# LM74910H_PINOUT.net
KiCad netlist of a schematic drawn in Altium Designer
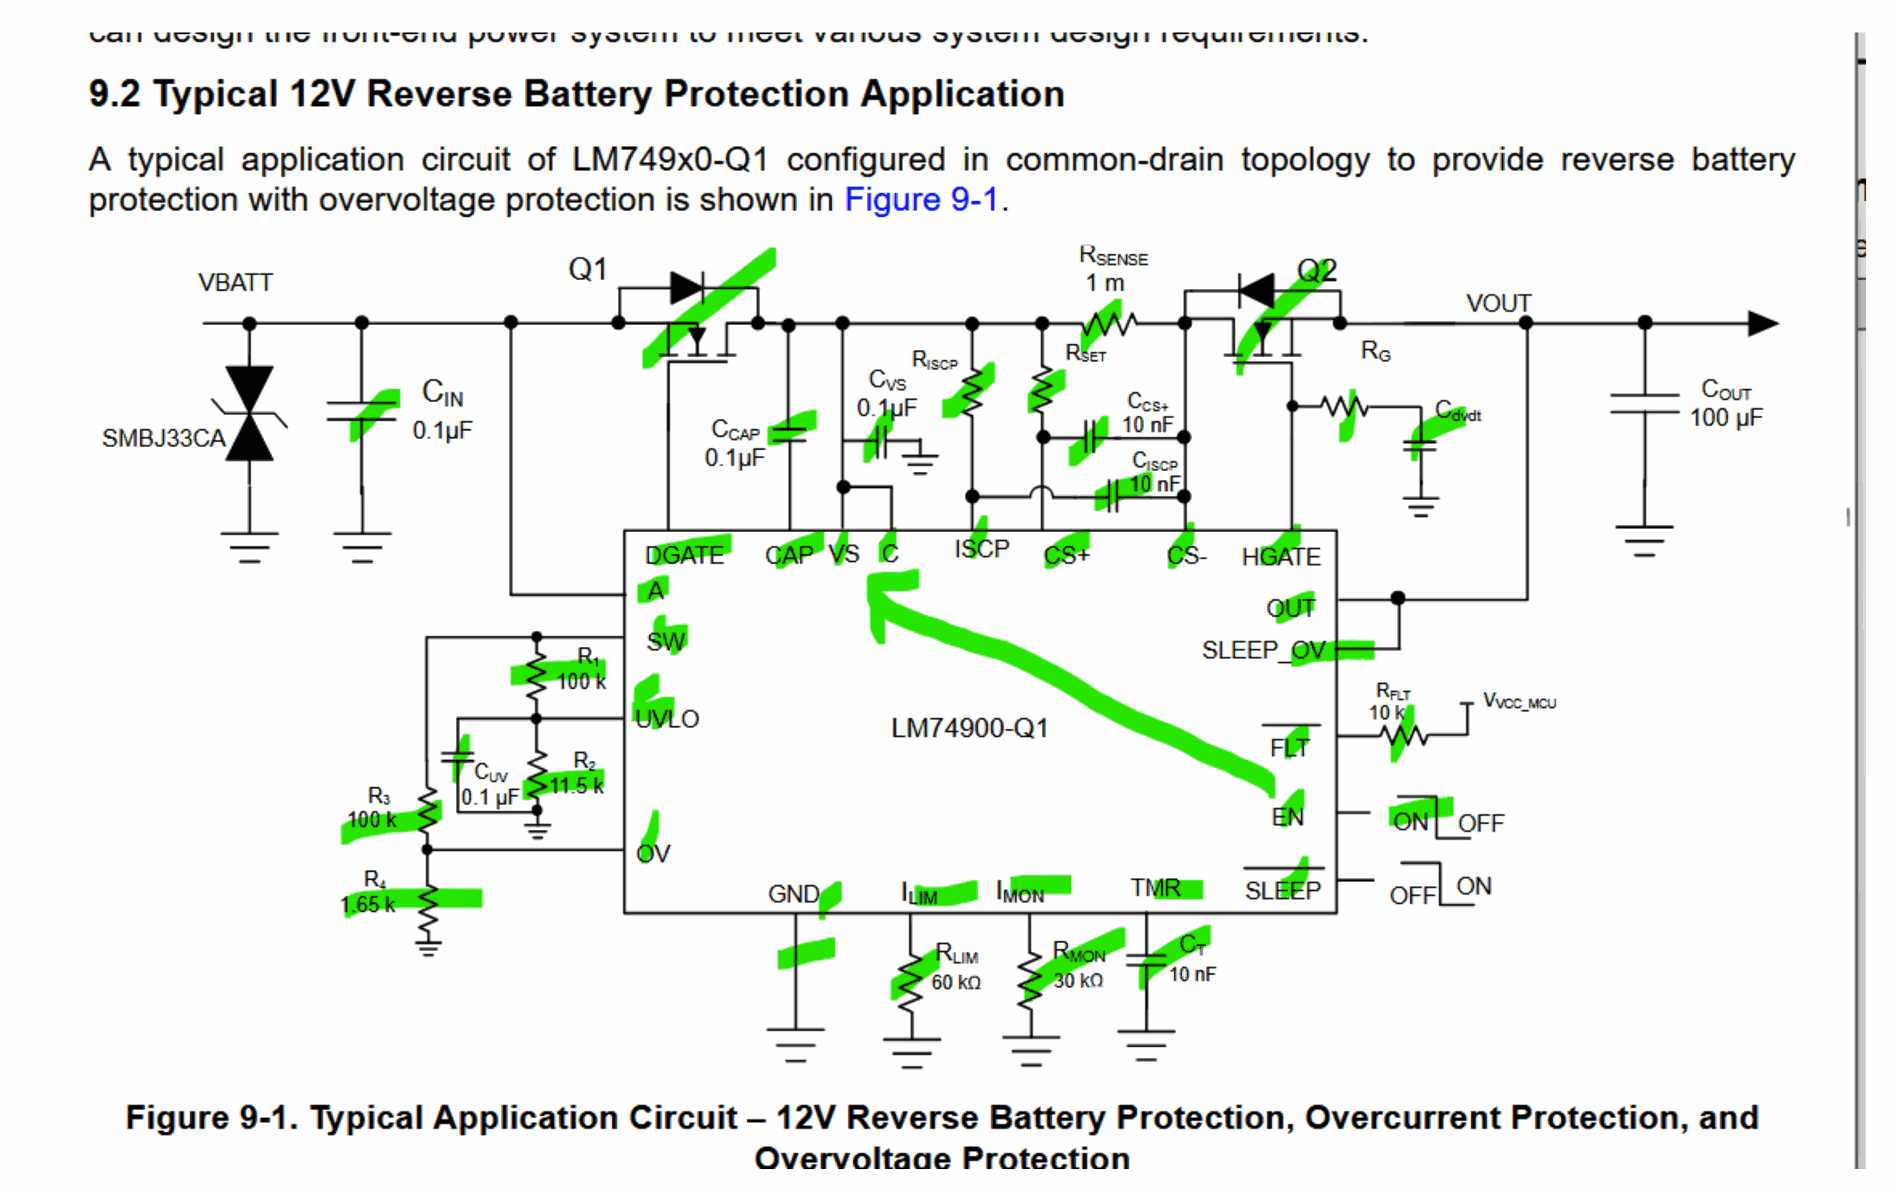
[diagram p0: LM74910H_PINOUT.SchDoc, top]
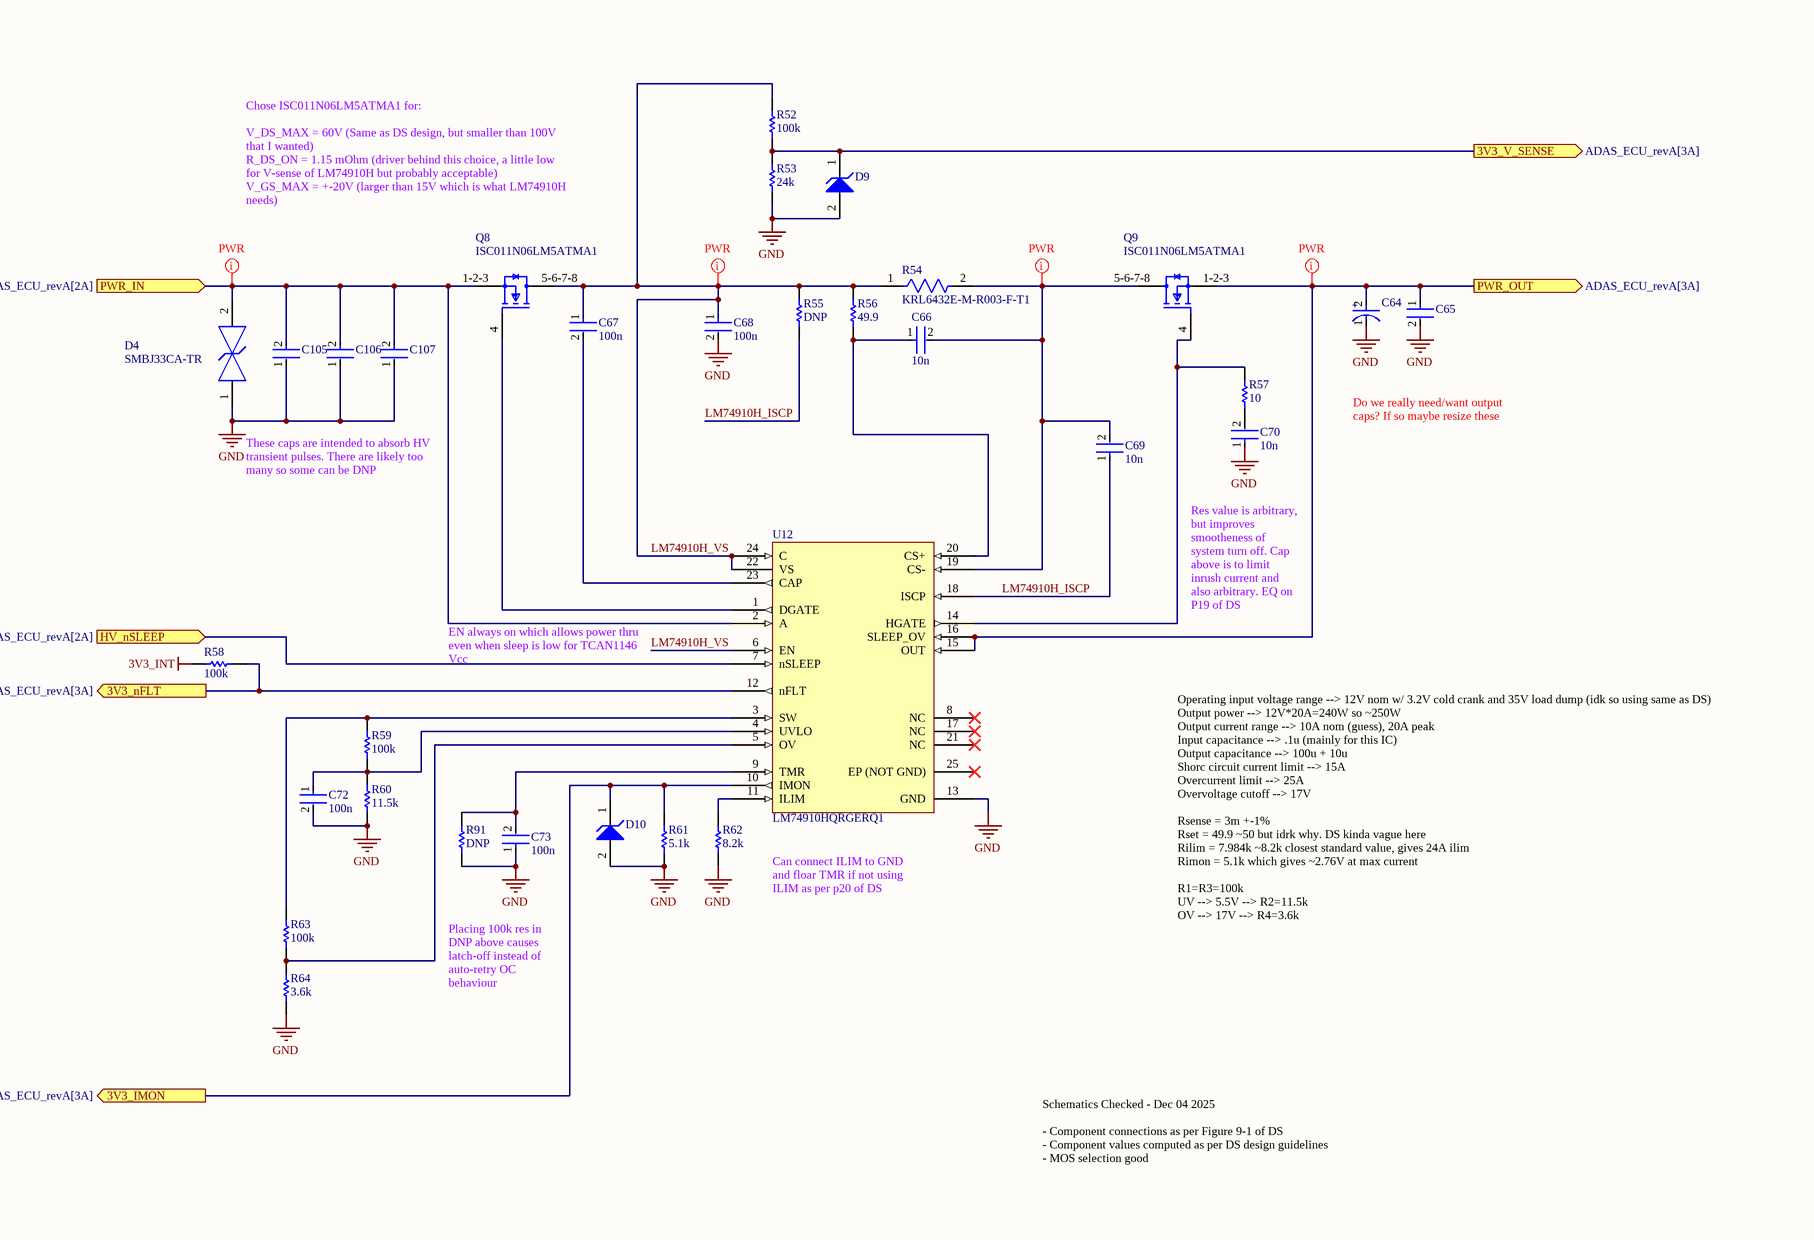
[diagram p1: LM74910H_PINOUT.SchDoc, bottom]

(export (version "E")
  (design (tool "Eeschema 10.0.6"))
  (components
    (comp (ref "C64")
      (value "EEE-FK1H100UR")
      (footprint "FP-FKC-MFG")
      (description "CAP ALUM 10UF 20% 50V SMD")
      (fields (field (name "TOLERANCE") "20%") (field (name "VOLTAGE") "50V"))
      (libsource (lib "Altium Content Vault") (part "a00bbbee19879c290e62620ae7e47b1"))
    )
    (comp (ref "C65")
      (value "12103D106KAT2A")
      (footprint "FP-1210-L_3_3_0_4-W_2_5_0-MFG")
      (description "General Purpose Ceramic Capacitor, 1210, 10uF, 10%, X5R, 15%, 25V")
      (fields (field (name "VOLTAGE") "25V") (field (name "TOLERANCE") "10%"))
      (libsource (lib "Altium Content Vault") (part "b4654b650e69147ec39a6b967a45e02"))
    )
    (comp (ref "C66")
      (value "10n")
      (footprint "FP-0402-L_1_0_0_05-W_0_5-IPC_A")
      (description "LARGE PADS, 0402 CAP, CHANGE COMMENT TO MATCH REAL P/N")
      (libsource (lib "Space Concordia") (part "b4654b650e69147ec39a6b967a45e02"))
    )
    (comp (ref "C67")
      (value "100n")
      (footprint "FP-0402-L_1_0_0_05-W_0_5-IPC_A")
      (description "LARGE PADS, 0402 CAP, CHANGE COMMENT TO MATCH REAL P/N")
      (libsource (lib "Space Concordia") (part "b4654b650e69147ec39a6b967a45e02"))
    )
    (comp (ref "C68")
      (value "100n")
      (footprint "FP-0402-L_1_0_0_05-W_0_5-IPC_A")
      (description "LARGE PADS, 0402 CAP, CHANGE COMMENT TO MATCH REAL P/N")
      (libsource (lib "Space Concordia") (part "b4654b650e69147ec39a6b967a45e02"))
    )
    (comp (ref "C69")
      (value "10n")
      (footprint "FP-0402-L_1_0_0_05-W_0_5-IPC_A")
      (description "LARGE PADS, 0402 CAP, CHANGE COMMENT TO MATCH REAL P/N")
      (libsource (lib "Space Concordia") (part "b4654b650e69147ec39a6b967a45e02"))
    )
    (comp (ref "C70")
      (value "10n")
      (footprint "FP-0402-L_1_0_0_05-W_0_5-IPC_A")
      (description "LARGE PADS, 0402 CAP, CHANGE COMMENT TO MATCH REAL P/N")
      (libsource (lib "Space Concordia") (part "b4654b650e69147ec39a6b967a45e02"))
    )
    (comp (ref "C72")
      (value "100n")
      (footprint "FP-0402-L_1_0_0_05-W_0_5-IPC_A")
      (description "LARGE PADS, 0402 CAP, CHANGE COMMENT TO MATCH REAL P/N")
      (libsource (lib "Space Concordia") (part "b4654b650e69147ec39a6b967a45e02"))
    )
    (comp (ref "C73")
      (value "100n")
      (footprint "FP-0402-L_1_0_0_05-W_0_5-IPC_A")
      (description "LARGE PADS, 0402 CAP, CHANGE COMMENT TO MATCH REAL P/N")
      (libsource (lib "Space Concordia") (part "b4654b650e69147ec39a6b967a45e02"))
    )
    (comp (ref "C105")
      (value "AC1210KKX7R0BB104")
      (footprint "FP-AC1210-0_85-MFG")
      (description "CAP CER 0.1UF 100V X7R 1210")
      (fields (field (name "MANUFACTURER") "Yageo") (field (name "TOLERANCE") "0.1"))
      (libsource (lib "Altium Content Vault") (part "236180d848d6139a670b325ea6854c9"))
    )
    (comp (ref "C106")
      (value "AC1210KKX7R0BB104")
      (footprint "FP-AC1210-0_85-MFG")
      (description "CAP CER 0.1UF 100V X7R 1210")
      (fields (field (name "MANUFACTURER") "Yageo") (field (name "TOLERANCE") "0.1"))
      (libsource (lib "Altium Content Vault") (part "236180d848d6139a670b325ea6854c9"))
    )
    (comp (ref "C107")
      (value "AC1210KKX7R0BB104")
      (footprint "FP-AC1210-0_85-MFG")
      (description "CAP CER 0.1UF 100V X7R 1210")
      (fields (field (name "MANUFACTURER") "Yageo") (field (name "TOLERANCE") "0.1"))
      (libsource (lib "Altium Content Vault") (part "236180d848d6139a670b325ea6854c9"))
    )
    (comp (ref "D4")
      (value "SMBJ33CA-TR")
      (footprint "FP-SMB-CA-MFG")
      (description "TVS DIODE 33V 69.7V SMB")
      (fields
        (field (name "OCTOPART") "https://octopart.com/smbj33ca-tr-stmicroelectronics-347069")
        (field (name "MANUFACTURER") "STMicroelectronics")
      )
      (libsource (lib "Altium Content Vault") (part "11bd9d59d340f0612179daf16ad9b72"))
    )
    (comp (ref "D9")
      (value "DNP/MM5Z3V3T1G")
      (footprint "ONSC-SOD-523-2-502-01_V")
      (description "Zener Voltage Regulator, 500 mW, 2-Pin SOD-523, Pb-Free, Tape and Reel")
      (fields (field (name "MANUFACTURER") "On Semiconductor") (field (name "PARTNUMBER") "MM5Z3V3T1G"))
      (libsource (lib "Altium Content Vault") (part "ONSC-K1A2-2"))
    )
    (comp (ref "D10")
      (value "DNP/MM5Z3V3T1G")
      (footprint "ONSC-SOD-523-2-502-01_V")
      (description "Zener Voltage Regulator, 500 mW, 2-Pin SOD-523, Pb-Free, Tape and Reel")
      (fields (field (name "MANUFACTURER") "On Semiconductor") (field (name "PARTNUMBER") "MM5Z3V3T1G"))
      (libsource (lib "Altium Content Vault") (part "ONSC-K1A2-2"))
    )
    (comp (ref "Q8")
      (value "ISC011N06LM5ATMA1")
      (footprint "FP-PG-TDSON-8-MFG")
      (description "TRENCH 40<-<100V PG-TDSON-8")
      (libsource (lib "Altium Content Vault") (part "3085234d4498bcd04bc7e5400bb7c96"))
    )
    (comp (ref "Q9")
      (value "ISC011N06LM5ATMA1")
      (footprint "FP-PG-TDSON-8-MFG")
      (description "TRENCH 40<-<100V PG-TDSON-8")
      (libsource (lib "Altium Content Vault") (part "3085234d4498bcd04bc7e5400bb7c96"))
    )
    (comp (ref "R52")
      (value "100k")
      (footprint "R0603B")
      (description "Resistor")
      (libsource (lib "Space Concordia") (part "Resistor"))
    )
    (comp (ref "R53")
      (value "24k")
      (footprint "R0603B")
      (description "Resistor")
      (libsource (lib "Space Concordia") (part "Resistor"))
    )
    (comp (ref "R54")
      (value "KRL6432E-M-R003-F-T1")
      (footprint "FP-KRL6432E-MFG")
      (description "KRL6432E-M-R003-F-T1 Metal Foil Low Resistance Chip Resistor (long-side terminal), 2512, RoHS")
      (fields (field (name "TOLERANCE") "1%"))
      (libsource (lib "Altium Content Vault") (part "1029c3af85768c4190bb7ad29bc67b5"))
    )
    (comp (ref "R55")
      (value "DNP")
      (footprint "R0603B")
      (description "Resistor")
      (libsource (lib "Space Concordia") (part "Resistor"))
    )
    (comp (ref "R56")
      (value "49.9")
      (footprint "R0603B")
      (description "Resistor")
      (libsource (lib "Space Concordia") (part "Resistor"))
    )
    (comp (ref "R57")
      (value "10")
      (footprint "R0603B")
      (description "Resistor")
      (libsource (lib "Space Concordia") (part "Resistor"))
    )
    (comp (ref "R58")
      (value "100k")
      (footprint "R0603B")
      (description "Resistor")
      (libsource (lib "Space Concordia") (part "Resistor"))
    )
    (comp (ref "R59")
      (value "100k")
      (footprint "R0603B")
      (description "Resistor")
      (libsource (lib "Space Concordia") (part "Resistor"))
    )
    (comp (ref "R60")
      (value "11.5k")
      (footprint "R0603B")
      (description "Resistor")
      (libsource (lib "Space Concordia") (part "Resistor"))
    )
    (comp (ref "R61")
      (value "5.1k")
      (footprint "R0603B")
      (description "Resistor")
      (libsource (lib "Space Concordia") (part "Resistor"))
    )
    (comp (ref "R62")
      (value "8.2k")
      (footprint "R0603B")
      (description "Resistor")
      (libsource (lib "Space Concordia") (part "Resistor"))
    )
    (comp (ref "R63")
      (value "100k")
      (footprint "R0603B")
      (description "Resistor")
      (libsource (lib "Space Concordia") (part "Resistor"))
    )
    (comp (ref "R64")
      (value "3.6k")
      (footprint "R0603B")
      (description "Resistor")
      (libsource (lib "Space Concordia") (part "Resistor"))
    )
    (comp (ref "R91")
      (value "DNP")
      (footprint "R0603B")
      (description "Resistor")
      (libsource (lib "Space Concordia") (part "Resistor"))
    )
    (comp (ref "U12")
      (value "LM74910HQRGERQ1")
      (footprint "QFN50P400X400X100_HS-25N")
      (libsource (lib "Space Concordia") (part "LM74910HQRGERQ1"))
    )
  )
  (nets
    (net (code "1") (name "/3V3_IMON") (class "Default")
      (node (ref "D10") (pin "1") (pinfunction "K_1") (pintype "passive"))
      (node (ref "R61") (pin "2") (pinfunction "2_2") (pintype "passive"))
      (node (ref "U12") (pin "10") (pinfunction "IMON_10") (pintype "output"))
    )
    (net (code "2") (name "/3V3_V_SENSE") (class "Default")
      (node (ref "D9") (pin "1") (pinfunction "K_1") (pintype "passive"))
      (node (ref "R52") (pin "1") (pinfunction "1_1") (pintype "passive"))
      (node (ref "R53") (pin "2") (pinfunction "2_2") (pintype "passive"))
    )
    (net (code "3") (name "/3V3_nFLT") (class "Default")
      (node (ref "R58") (pin "1") (pinfunction "1_1") (pintype "passive"))
      (node (ref "U12") (pin "12") (pinfunction "nFLT_12") (pintype "output"))
    )
    (net (code "4") (name "/HV_nSLEEP") (class "Default")
      (node (ref "U12") (pin "7") (pinfunction "nSLEEP_7") (pintype "input"))
    )
    (net (code "5") (name "/LM74910H_ISCP") (class "Default")
      (node (ref "C69") (pin "1") (pinfunction "1_1") (pintype "passive"))
      (node (ref "R55") (pin "1") (pinfunction "1_1") (pintype "passive"))
      (node (ref "U12") (pin "18") (pinfunction "ISCP_18") (pintype "input"))
    )
    (net (code "6") (name "/LM74910H_VS") (class "Default")
      (node (ref "C67") (pin "1") (pinfunction "1_1") (pintype "passive"))
      (node (ref "C68") (pin "1") (pinfunction "1_1") (pintype "passive"))
      (node (ref "Q8") (pin "5-6-7-8") (pinfunction "D_5-6-7-8") (pintype "passive"))
      (node (ref "R52") (pin "2") (pinfunction "2_2") (pintype "passive"))
      (node (ref "R54") (pin "1") (pinfunction "1_1") (pintype "passive"))
      (node (ref "R55") (pin "2") (pinfunction "2_2") (pintype "passive"))
      (node (ref "R56") (pin "2") (pinfunction "2_2") (pintype "passive"))
      (node (ref "U12") (pin "22") (pinfunction "VS_22") (pintype "power_in"))
      (node (ref "U12") (pin "24") (pinfunction "C_24") (pintype "input"))
      (node (ref "U12") (pin "6") (pinfunction "EN_6") (pintype "input"))
    )
    (net (code "7") (name "/PWR_IN") (class "Default")
      (node (ref "C105") (pin "2") (pinfunction "2_2") (pintype "passive"))
      (node (ref "C106") (pin "2") (pinfunction "2_2") (pintype "passive"))
      (node (ref "C107") (pin "2") (pinfunction "2_2") (pintype "passive"))
      (node (ref "D4") (pin "2") (pinfunction "2_2") (pintype "passive"))
      (node (ref "Q8") (pin "1-2-3") (pinfunction "S_1-2-3") (pintype "passive"))
      (node (ref "U12") (pin "2") (pinfunction "A_2") (pintype "input"))
    )
    (net (code "8") (name "/PWR_OUT") (class "Default")
      (node (ref "C64") (pin "2") (pinfunction "A_2") (pintype "passive"))
      (node (ref "C65") (pin "1") (pinfunction "1_1") (pintype "passive"))
      (node (ref "Q9") (pin "1-2-3") (pinfunction "S_1-2-3") (pintype "passive"))
      (node (ref "U12") (pin "15") (pinfunction "OUT_15") (pintype "input"))
      (node (ref "U12") (pin "16") (pinfunction "SLEEP_OV_16") (pintype "input"))
    )
    (net (code "9") (name "3V3_INT") (class "Default")
      (node (ref "R58") (pin "2") (pinfunction "2_2") (pintype "passive"))
    )
    (net (code "10") (name "GND") (class "Default")
      (node (ref "C105") (pin "1") (pinfunction "1_1") (pintype "passive"))
      (node (ref "C106") (pin "1") (pinfunction "1_1") (pintype "passive"))
      (node (ref "C107") (pin "1") (pinfunction "1_1") (pintype "passive"))
      (node (ref "C64") (pin "1") (pinfunction "C_1") (pintype "passive"))
      (node (ref "C65") (pin "2") (pinfunction "2_2") (pintype "passive"))
      (node (ref "C68") (pin "2") (pinfunction "2_2") (pintype "passive"))
      (node (ref "C70") (pin "1") (pinfunction "1_1") (pintype "passive"))
      (node (ref "C72") (pin "2") (pinfunction "2_2") (pintype "passive"))
      (node (ref "C73") (pin "1") (pinfunction "1_1") (pintype "passive"))
      (node (ref "D10") (pin "2") (pinfunction "A_2") (pintype "passive"))
      (node (ref "D4") (pin "1") (pinfunction "1_1") (pintype "passive"))
      (node (ref "D9") (pin "2") (pinfunction "A_2") (pintype "passive"))
      (node (ref "R53") (pin "1") (pinfunction "1_1") (pintype "passive"))
      (node (ref "R60") (pin "1") (pinfunction "1_1") (pintype "passive"))
      (node (ref "R61") (pin "1") (pinfunction "1_1") (pintype "passive"))
      (node (ref "R62") (pin "1") (pinfunction "1_1") (pintype "passive"))
      (node (ref "R64") (pin "1") (pinfunction "1_1") (pintype "passive"))
      (node (ref "R91") (pin "1") (pinfunction "1_1") (pintype "passive"))
      (node (ref "U12") (pin "13") (pinfunction "GND_13") (pintype "power_in"))
    )
    (net (code "11") (name "Net-(C70-Pad2)") (class "Default")
      (node (ref "C70") (pin "2") (pinfunction "2_2") (pintype "passive"))
      (node (ref "R57") (pin "1") (pinfunction "1_1") (pintype "passive"))
    )
    (net (code "12") (name "Net-(Q8-G)") (class "Default")
      (node (ref "Q8") (pin "4") (pinfunction "G_4") (pintype "passive"))
      (node (ref "U12") (pin "1") (pinfunction "DGATE_1") (pintype "output"))
    )
    (net (code "13") (name "Net-(Q9-D)") (class "Default")
      (node (ref "C66") (pin "2") (pinfunction "2_2") (pintype "passive"))
      (node (ref "C69") (pin "2") (pinfunction "2_2") (pintype "passive"))
      (node (ref "Q9") (pin "5-6-7-8") (pinfunction "D_5-6-7-8") (pintype "passive"))
      (node (ref "R54") (pin "2") (pinfunction "2_2") (pintype "passive"))
      (node (ref "U12") (pin "19") (pinfunction "CS-_19") (pintype "input"))
    )
    (net (code "14") (name "Net-(Q9-G)") (class "Default")
      (node (ref "Q9") (pin "4") (pinfunction "G_4") (pintype "passive"))
      (node (ref "R57") (pin "2") (pinfunction "2_2") (pintype "passive"))
      (node (ref "U12") (pin "14") (pinfunction "HGATE_14") (pintype "output"))
    )
    (net (code "15") (name "Net-(U12-CAP)") (class "Default")
      (node (ref "C67") (pin "2") (pinfunction "2_2") (pintype "passive"))
      (node (ref "U12") (pin "23") (pinfunction "CAP_23") (pintype "output"))
    )
    (net (code "16") (name "Net-(U12-CS+)") (class "Default")
      (node (ref "C66") (pin "1") (pinfunction "1_1") (pintype "passive"))
      (node (ref "R56") (pin "1") (pinfunction "1_1") (pintype "passive"))
      (node (ref "U12") (pin "20") (pinfunction "CS+_20") (pintype "input"))
    )
    (net (code "17") (name "Net-(U12-ILIM)") (class "Default")
      (node (ref "R62") (pin "2") (pinfunction "2_2") (pintype "passive"))
      (node (ref "U12") (pin "11") (pinfunction "ILIM_11") (pintype "input"))
    )
    (net (code "18") (name "Net-(U12-OV)") (class "Default")
      (node (ref "R63") (pin "1") (pinfunction "1_1") (pintype "passive"))
      (node (ref "R64") (pin "2") (pinfunction "2_2") (pintype "passive"))
      (node (ref "U12") (pin "5") (pinfunction "OV_5") (pintype "input"))
    )
    (net (code "19") (name "Net-(U12-SW)") (class "Default")
      (node (ref "R59") (pin "2") (pinfunction "2_2") (pintype "passive"))
      (node (ref "R63") (pin "2") (pinfunction "2_2") (pintype "passive"))
      (node (ref "U12") (pin "3") (pinfunction "SW_3") (pintype "input"))
    )
    (net (code "20") (name "Net-(U12-TMR)") (class "Default")
      (node (ref "C73") (pin "2") (pinfunction "2_2") (pintype "passive"))
      (node (ref "R91") (pin "2") (pinfunction "2_2") (pintype "passive"))
      (node (ref "U12") (pin "9") (pinfunction "TMR_9") (pintype "input"))
    )
    (net (code "21") (name "Net-(U12-UVLO)") (class "Default")
      (node (ref "C72") (pin "1") (pinfunction "1_1") (pintype "passive"))
      (node (ref "R59") (pin "1") (pinfunction "1_1") (pintype "passive"))
      (node (ref "R60") (pin "2") (pinfunction "2_2") (pintype "passive"))
      (node (ref "U12") (pin "4") (pinfunction "UVLO_4") (pintype "input"))
    )
    (net (code "22") (name "unconnected-(U12-EP_(NOT_GND)-Pad25)") (class "Default")
      (node (ref "U12") (pin "25") (pinfunction "EP_(NOT_GND)_25") (pintype "passive+no_connect"))
    )
    (net (code "23") (name "unconnected-(U12-NC-Pad8)") (class "Default")
      (node (ref "U12") (pin "8") (pinfunction "NC_8") (pintype "passive+no_connect"))
    )
    (net (code "24") (name "unconnected-(U12-NC-Pad17)") (class "Default")
      (node (ref "U12") (pin "17") (pinfunction "NC_17") (pintype "passive+no_connect"))
    )
    (net (code "25") (name "unconnected-(U12-NC-Pad21)") (class "Default")
      (node (ref "U12") (pin "21") (pinfunction "NC_21") (pintype "passive+no_connect"))
    )
  )
)
